# pcb-name-card-sp.net
KiCad netlist of a schematic drawn in EAGLE
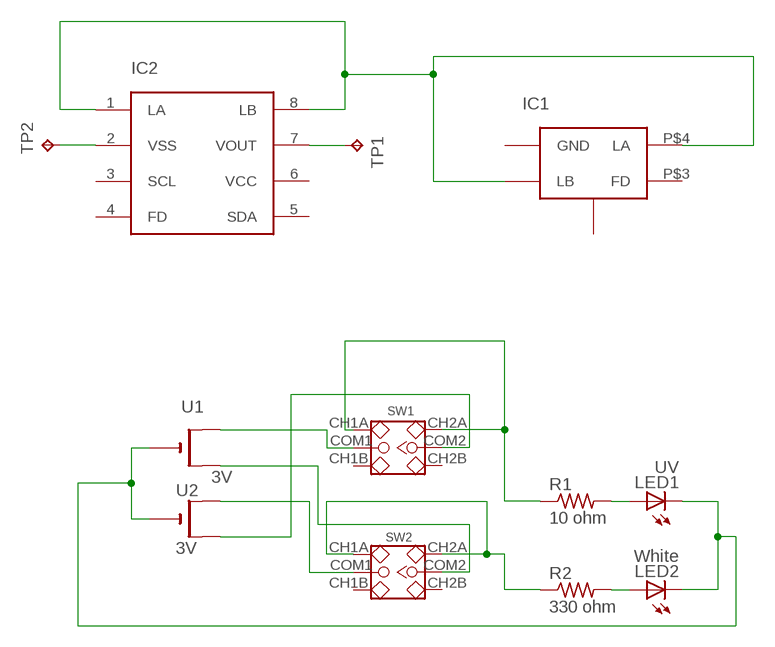
[diagram p0: schematic, sheet 1]

(export (version "E")
  (design (tool "Eeschema 10.0.6"))
  (components
    (comp (ref "IC1")
      (value "NTAG21XFDRC-FIT")
      (footprint "eagle-import:HXSON4-SMALL")
      (libsource (lib "eagle-import") (part "NTAG21XFDRC-FIT"))
    )
    (comp (ref "IC2")
      (value "NT3H1X01W0FTT")
      (footprint "eagle-import:TSSOP-8")
      (libsource (lib "eagle-import") (part "NT3H1X01W0FTT"))
    )
    (comp (ref "LED1")
      (value "UV")
      (footprint "eagle-import:PLCC2")
      (libsource (lib "eagle-import") (part "_T679-?-1D2E2LY"))
    )
    (comp (ref "LED2")
      (value "White")
      (footprint "eagle-import:PLCC2")
      (libsource (lib "eagle-import") (part "_T679-?-1D2E2LY"))
    )
    (comp (ref "R1")
      (value "10 ohm")
      (footprint "eagle-import:R2010")
      (libsource (lib "eagle-import") (part "R-US_R2010"))
    )
    (comp (ref "R2")
      (value "330 ohm")
      (footprint "eagle-import:R2010")
      (libsource (lib "eagle-import") (part "R-US_R2010"))
    )
    (comp (ref "SW1")
      (value "SMD-TOGGLE-SWITCH-2CH(2X3P-7X3.5MM)")
      (footprint "eagle-import:SW6-2.54-SMD-7.0X3.5X1.5MM")
      (fields (field (name "MPN") "MS-22C01"))
      (libsource (lib "eagle-import") (part "SMD-TOGGLE-SWITCH-2CH(2X3P-7X3.5MM)"))
    )
    (comp (ref "SW2")
      (value "SMD-TOGGLE-SWITCH-2CH(2X3P-7X3.5MM)")
      (footprint "eagle-import:SW6-2.54-SMD-7.0X3.5X1.5MM")
      (fields (field (name "MPN") "MS-22C01"))
      (libsource (lib "eagle-import") (part "SMD-TOGGLE-SWITCH-2CH(2X3P-7X3.5MM)"))
    )
    (comp (ref "TP1")
      (value "VOUT")
      (footprint "eagle-import:B2,54")
      (libsource (lib "eagle-import") (part "TPB2,54"))
    )
    (comp (ref "TP2")
      (value "GND")
      (footprint "eagle-import:B2,54")
      (libsource (lib "eagle-import") (part "TPB2,54"))
    )
    (comp (ref "U1")
      (value "3V")
      (footprint "eagle-import:CR2032-SMD")
      (libsource (lib "eagle-import") (part "CR2032SMT"))
    )
    (comp (ref "U2")
      (value "3V")
      (footprint "eagle-import:CR2032-SMD")
      (libsource (lib "eagle-import") (part "CR2032SMT"))
    )
  )
  (nets
    (net (code "1") (name "Net-(IC1-LA)") (class "Default")
      (node (ref "IC1") (pin "P$2") (pinfunction "LB_P$2") (pintype "bidirectional"))
      (node (ref "IC1") (pin "P$4") (pinfunction "LA_P$4") (pintype "bidirectional"))
      (node (ref "IC2") (pin "1") (pinfunction "LA_1") (pintype "bidirectional"))
      (node (ref "IC2") (pin "8") (pinfunction "LB_8") (pintype "bidirectional"))
    )
    (net (code "2") (name "Net-(IC2-VOUT)") (class "Default")
      (node (ref "IC2") (pin "7") (pinfunction "VOUT_7") (pintype "bidirectional"))
      (node (ref "TP1") (pin "TP") (pinfunction "TP_TP") (pintype "input"))
    )
    (net (code "3") (name "Net-(IC2-VSS)") (class "Default")
      (node (ref "IC2") (pin "2") (pinfunction "VSS_2") (pintype "bidirectional"))
      (node (ref "TP2") (pin "TP") (pinfunction "TP_TP") (pintype "input"))
    )
    (net (code "4") (name "Net-(LED1-PadA)") (class "Default")
      (node (ref "LED1") (pin "A") (pinfunction "A_A") (pintype "passive"))
      (node (ref "R1") (pin "2") (pinfunction "2_2") (pintype "passive"))
    )
    (net (code "5") (name "Net-(LED1-PadC)") (class "Default")
      (node (ref "LED1") (pin "C") (pinfunction "C_C") (pintype "passive"))
      (node (ref "LED2") (pin "C") (pinfunction "C_C") (pintype "passive"))
      (node (ref "U1") (pin "-") (pinfunction "-_-") (pintype "passive"))
      (node (ref "U2") (pin "-") (pinfunction "-_-") (pintype "passive"))
    )
    (net (code "6") (name "Net-(LED2-PadA)") (class "Default")
      (node (ref "LED2") (pin "A") (pinfunction "A_A") (pintype "passive"))
      (node (ref "R2") (pin "2") (pinfunction "2_2") (pintype "passive"))
    )
    (net (code "7") (name "Net-(R1-Pad1)") (class "Default")
      (node (ref "R1") (pin "1") (pinfunction "1_1") (pintype "passive"))
      (node (ref "SW1") (pin "CH1A") (pinfunction "CH1A_CH1A") (pintype "bidirectional"))
      (node (ref "SW1") (pin "CH2A") (pinfunction "CH2A_CH2A") (pintype "bidirectional"))
    )
    (net (code "8") (name "Net-(R2-Pad1)") (class "Default")
      (node (ref "R2") (pin "1") (pinfunction "1_1") (pintype "passive"))
      (node (ref "SW2") (pin "CH1A") (pinfunction "CH1A_CH1A") (pintype "bidirectional"))
      (node (ref "SW2") (pin "CH2A") (pinfunction "CH2A_CH2A") (pintype "bidirectional"))
    )
    (net (code "9") (name "Net-(U1-+)") (class "Default")
      (node (ref "SW1") (pin "COM1") (pinfunction "COM1_COM1") (pintype "bidirectional"))
      (node (ref "U1") (pin "+$1") (pinfunction "+_+$1") (pintype "passive"))
    )
    (net (code "10") (name "Net-(U1-+1)") (class "Default")
      (node (ref "SW2") (pin "COM2") (pinfunction "COM2_COM2") (pintype "bidirectional"))
      (node (ref "U1") (pin "+$2") (pinfunction "+1_+$2") (pintype "passive"))
    )
    (net (code "11") (name "Net-(U2-+)") (class "Default")
      (node (ref "SW2") (pin "COM1") (pinfunction "COM1_COM1") (pintype "bidirectional"))
      (node (ref "U2") (pin "+$1") (pinfunction "+_+$1") (pintype "passive"))
    )
    (net (code "12") (name "Net-(U2-+1)") (class "Default")
      (node (ref "SW1") (pin "COM2") (pinfunction "COM2_COM2") (pintype "bidirectional"))
      (node (ref "U2") (pin "+$2") (pinfunction "+1_+$2") (pintype "passive"))
    )
    (net (code "13") (name "unconnected-(IC1-FD-PadP$3)") (class "Default")
      (node (ref "IC1") (pin "P$3") (pinfunction "FD_P$3") (pintype "bidirectional"))
    )
    (net (code "14") (name "unconnected-(IC1-FLOAT-PadP$5)") (class "Default")
      (node (ref "IC1") (pin "P$5") (pinfunction "FLOAT_P$5") (pintype "bidirectional"))
    )
    (net (code "15") (name "unconnected-(IC1-GND-PadP$1)") (class "Default")
      (node (ref "IC1") (pin "P$1") (pinfunction "GND_P$1") (pintype "bidirectional"))
    )
    (net (code "16") (name "unconnected-(IC2-FD-Pad4)") (class "Default")
      (node (ref "IC2") (pin "4") (pinfunction "FD_4") (pintype "bidirectional"))
    )
    (net (code "17") (name "unconnected-(IC2-SCL-Pad3)") (class "Default")
      (node (ref "IC2") (pin "3") (pinfunction "SCL_3") (pintype "bidirectional"))
    )
    (net (code "18") (name "unconnected-(IC2-SDA-Pad5)") (class "Default")
      (node (ref "IC2") (pin "5") (pinfunction "SDA_5") (pintype "bidirectional"))
    )
    (net (code "19") (name "unconnected-(IC2-VCC-Pad6)") (class "Default")
      (node (ref "IC2") (pin "6") (pinfunction "VCC_6") (pintype "bidirectional"))
    )
    (net (code "20") (name "unconnected-(SW1-PadCH1B)") (class "Default")
      (node (ref "SW1") (pin "CH1B") (pinfunction "CH1B_CH1B") (pintype "bidirectional"))
    )
    (net (code "21") (name "unconnected-(SW1-PadCH2B)") (class "Default")
      (node (ref "SW1") (pin "CH2B") (pinfunction "CH2B_CH2B") (pintype "bidirectional"))
    )
    (net (code "22") (name "unconnected-(SW2-PadCH1B)") (class "Default")
      (node (ref "SW2") (pin "CH1B") (pinfunction "CH1B_CH1B") (pintype "bidirectional"))
    )
    (net (code "23") (name "unconnected-(SW2-PadCH2B)") (class "Default")
      (node (ref "SW2") (pin "CH2B") (pinfunction "CH2B_CH2B") (pintype "bidirectional"))
    )
  )
)
